# satshakit.net
KiCad netlist of a schematic drawn in EAGLE
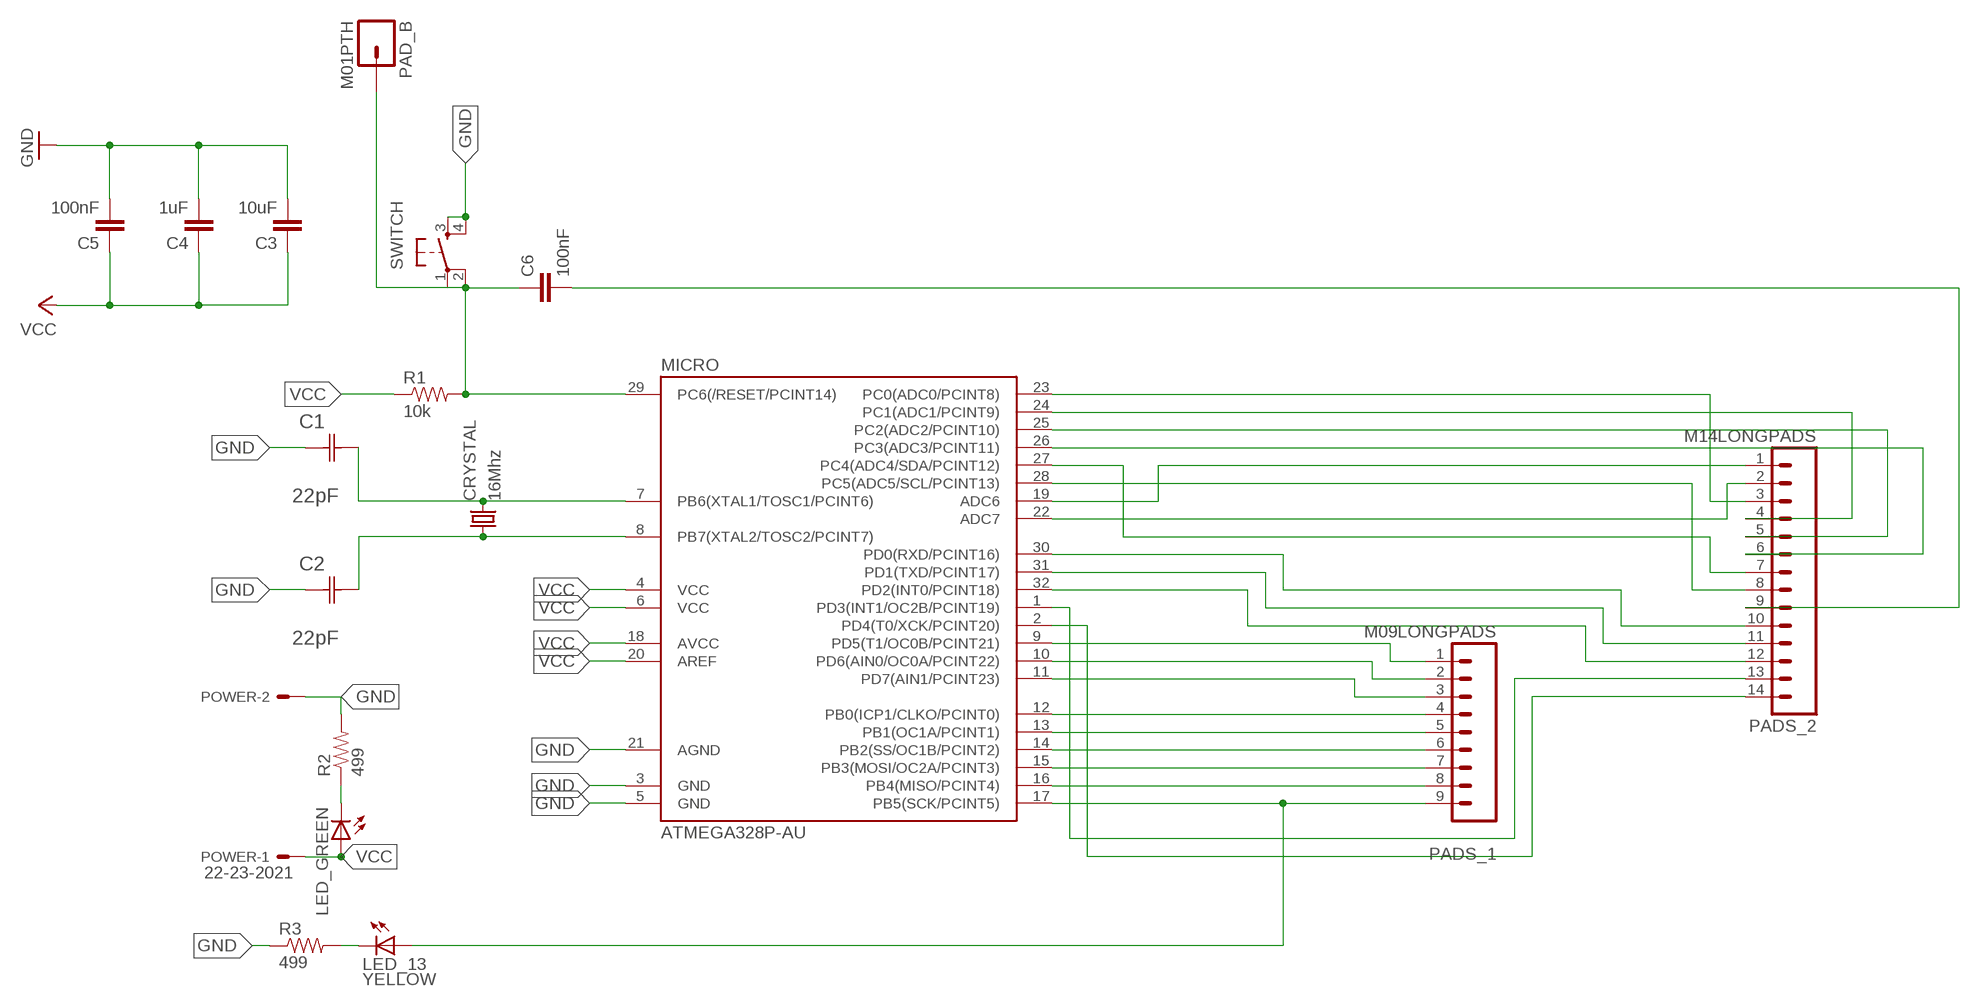
[diagram p0: schematic, sheet 1]

(export (version "E")
  (design (tool "Eeschema 10.0.6"))
  (components
    (comp (ref "C1")
      (value "22pF")
      (footprint "eagle-import:CAPC3216X178N")
      (fields (field (name "MPN") "0612ZC225MAT2A") (field (name "TOLERANCE") "±20%"))
      (libsource (lib "eagle-import") (part "0612ZC225MAT2A"))
    )
    (comp (ref "C2")
      (value "22pF")
      (footprint "eagle-import:CAPC3216X178N")
      (fields (field (name "MPN") "0612ZC225MAT2A") (field (name "TOLERANCE") "±20%"))
      (libsource (lib "eagle-import") (part "0612ZC225MAT2A"))
    )
    (comp (ref "C3")
      (value "10uF")
      (footprint "eagle-import:1206")
      (libsource (lib "eagle-import") (part "CAP1206"))
    )
    (comp (ref "C4")
      (value "1uF")
      (footprint "eagle-import:1206")
      (libsource (lib "eagle-import") (part "CAP1206"))
    )
    (comp (ref "C5")
      (value "100nF")
      (footprint "eagle-import:1206")
      (libsource (lib "eagle-import") (part "CAP1206"))
    )
    (comp (ref "C6")
      (value "100nF")
      (footprint "eagle-import:1206")
      (libsource (lib "eagle-import") (part "CAP1206"))
    )
    (comp (ref "CRYSTAL")
      (value "16Mhz")
      (footprint "eagle-import:CSM-7X-DU")
      (libsource (lib "eagle-import") (part "CSM-7X-DU"))
    )
    (comp (ref "LED_13")
      (value "YELLOW")
      (footprint "eagle-import:1206")
      (libsource (lib "eagle-import") (part "LED1206"))
    )
    (comp (ref "LED_GREEN")
      (value "LED1206")
      (footprint "eagle-import:1206")
      (libsource (lib "eagle-import") (part "LED1206"))
    )
    (comp (ref "MICRO")
      (value "ATMEGA328P-AU")
      (footprint "eagle-import:TQFP32-08")
      (libsource (lib "eagle-import") (part "ATMEGA48/88/168-AU"))
    )
    (comp (ref "PADS_1")
      (value "M09LONGPADS")
      (footprint "eagle-import:1X09_LONGPADS")
      (libsource (lib "eagle-import") (part "M09LONGPADS"))
    )
    (comp (ref "PADS_2")
      (value "M14LONGPADS")
      (footprint "eagle-import:1X14-LONGPADS")
      (libsource (lib "eagle-import") (part "M14LONGPADS"))
    )
    (comp (ref "PAD_B")
      (value "M01PTH")
      (footprint "eagle-import:1X01")
      (libsource (lib "eagle-import") (part "M01PTH"))
    )
    (comp (ref "POWER")
      (value "22-23-2021")
      (footprint "eagle-import:22-23-2021")
      (fields (field (name "MF") "MOLEX"))
      (libsource (lib "eagle-import") (part "22-23-2021"))
    )
    (comp (ref "R1")
      (value "10k")
      (footprint "eagle-import:1206")
      (libsource (lib "eagle-import") (part "RESISTOR1206"))
    )
    (comp (ref "R2")
      (value "499")
      (footprint "eagle-import:1206")
      (libsource (lib "eagle-import") (part "RESISTOR1206"))
    )
    (comp (ref "R3")
      (value "499")
      (footprint "eagle-import:1206")
      (libsource (lib "eagle-import") (part "RESISTOR1206"))
    )
    (comp (ref "SWITCH")
      (value "6MM_SWITCH6MM_SWITCH")
      (footprint "eagle-import:6MM_SWITCH")
      (libsource (lib "eagle-import") (part "6MM_SWITCH6MM_SWITCH"))
    )
  )
  (nets
    (net (code "1") (name "GND") (class "Default")
      (node (ref "C1") (pin "1") (pinfunction "C1_1") (pintype "passive"))
      (node (ref "C2") (pin "1") (pinfunction "C1_1") (pintype "passive"))
      (node (ref "C3") (pin "2") (pinfunction "2_2") (pintype "passive"))
      (node (ref "C4") (pin "2") (pinfunction "2_2") (pintype "passive"))
      (node (ref "C5") (pin "2") (pinfunction "2_2") (pintype "passive"))
      (node (ref "MICRO") (pin "21") (pinfunction "AGND_21") (pintype "power_in"))
      (node (ref "MICRO") (pin "3") (pinfunction "GND_3") (pintype "power_in"))
      (node (ref "MICRO") (pin "5") (pinfunction "GND_5") (pintype "power_in"))
      (node (ref "POWER") (pin "2") (pinfunction "S_2") (pintype "passive"))
      (node (ref "R2") (pin "2") (pinfunction "2_2") (pintype "passive"))
      (node (ref "R3") (pin "1") (pinfunction "1_1") (pintype "passive"))
      (node (ref "SWITCH") (pin "3") (pinfunction "S_3") (pintype "passive"))
      (node (ref "SWITCH") (pin "4") (pinfunction "S1_4") (pintype "passive"))
    )
    (net (code "2") (name "Net-(C1-C2)") (class "Default")
      (node (ref "C1") (pin "2") (pinfunction "C2_2") (pintype "passive"))
      (node (ref "CRYSTAL") (pin "2") (pinfunction "2_2") (pintype "passive"))
      (node (ref "MICRO") (pin "7") (pinfunction "PB6(XTAL1/TOSC1/PCINT6)_7") (pintype "bidirectional"))
    )
    (net (code "3") (name "Net-(C2-C2)") (class "Default")
      (node (ref "C2") (pin "2") (pinfunction "C2_2") (pintype "passive"))
      (node (ref "CRYSTAL") (pin "1") (pinfunction "1_1") (pintype "passive"))
      (node (ref "MICRO") (pin "8") (pinfunction "PB7(XTAL2/TOSC2/PCINT7)_8") (pintype "bidirectional"))
    )
    (net (code "4") (name "Net-(C6-Pad2)") (class "Default")
      (node (ref "C6") (pin "2") (pinfunction "2_2") (pintype "passive"))
      (node (ref "PADS_2") (pin "9") (pinfunction "9_9") (pintype "passive"))
    )
    (net (code "5") (name "Net-(LED_13-A)") (class "Default")
      (node (ref "LED_13") (pin "1") (pinfunction "A_1") (pintype "passive"))
      (node (ref "MICRO") (pin "17") (pinfunction "PB5(SCK/PCINT5)_17") (pintype "bidirectional"))
      (node (ref "PADS_1") (pin "9") (pinfunction "9_9") (pintype "passive"))
    )
    (net (code "6") (name "Net-(LED_13-C)") (class "Default")
      (node (ref "LED_13") (pin "2") (pinfunction "C_2") (pintype "passive"))
      (node (ref "R3") (pin "2") (pinfunction "2_2") (pintype "passive"))
    )
    (net (code "7") (name "Net-(LED_GREEN-C)") (class "Default")
      (node (ref "LED_GREEN") (pin "2") (pinfunction "C_2") (pintype "passive"))
      (node (ref "R2") (pin "1") (pinfunction "1_1") (pintype "passive"))
    )
    (net (code "8") (name "Net-(MICRO-ADC6)") (class "Default")
      (node (ref "MICRO") (pin "19") (pinfunction "ADC6_19") (pintype "passive"))
      (node (ref "PADS_2") (pin "1") (pinfunction "1_1") (pintype "passive"))
    )
    (net (code "9") (name "Net-(MICRO-ADC7)") (class "Default")
      (node (ref "MICRO") (pin "22") (pinfunction "ADC7_22") (pintype "passive"))
      (node (ref "PADS_2") (pin "2") (pinfunction "2_2") (pintype "passive"))
    )
    (net (code "10") (name "Net-(MICRO-PB0(ICP1{slash}CLKO{slash}PCINT0))") (class "Default")
      (node (ref "MICRO") (pin "12") (pinfunction "PB0(ICP1/CLKO/PCINT0)_12") (pintype "bidirectional"))
      (node (ref "PADS_1") (pin "4") (pinfunction "4_4") (pintype "passive"))
    )
    (net (code "11") (name "Net-(MICRO-PB1(OC1A{slash}PCINT1))") (class "Default")
      (node (ref "MICRO") (pin "13") (pinfunction "PB1(OC1A/PCINT1)_13") (pintype "bidirectional"))
      (node (ref "PADS_1") (pin "5") (pinfunction "5_5") (pintype "passive"))
    )
    (net (code "12") (name "Net-(MICRO-PB2(SS{slash}OC1B{slash}PCINT2))") (class "Default")
      (node (ref "MICRO") (pin "14") (pinfunction "PB2(SS/OC1B/PCINT2)_14") (pintype "bidirectional"))
      (node (ref "PADS_1") (pin "6") (pinfunction "6_6") (pintype "passive"))
    )
    (net (code "13") (name "Net-(MICRO-PB3(MOSI{slash}OC2A{slash}PCINT3))") (class "Default")
      (node (ref "MICRO") (pin "15") (pinfunction "PB3(MOSI/OC2A/PCINT3)_15") (pintype "bidirectional"))
      (node (ref "PADS_1") (pin "7") (pinfunction "7_7") (pintype "passive"))
    )
    (net (code "14") (name "Net-(MICRO-PB4(MISO{slash}PCINT4))") (class "Default")
      (node (ref "MICRO") (pin "16") (pinfunction "PB4(MISO/PCINT4)_16") (pintype "bidirectional"))
      (node (ref "PADS_1") (pin "8") (pinfunction "8_8") (pintype "passive"))
    )
    (net (code "15") (name "Net-(MICRO-PC0(ADC0{slash}PCINT8))") (class "Default")
      (node (ref "MICRO") (pin "23") (pinfunction "PC0(ADC0/PCINT8)_23") (pintype "bidirectional"))
      (node (ref "PADS_2") (pin "3") (pinfunction "3_3") (pintype "passive"))
    )
    (net (code "16") (name "Net-(MICRO-PC1(ADC1{slash}PCINT9))") (class "Default")
      (node (ref "MICRO") (pin "24") (pinfunction "PC1(ADC1/PCINT9)_24") (pintype "bidirectional"))
      (node (ref "PADS_2") (pin "4") (pinfunction "4_4") (pintype "passive"))
    )
    (net (code "17") (name "Net-(MICRO-PC2(ADC2{slash}PCINT10))") (class "Default")
      (node (ref "MICRO") (pin "25") (pinfunction "PC2(ADC2/PCINT10)_25") (pintype "bidirectional"))
      (node (ref "PADS_2") (pin "5") (pinfunction "5_5") (pintype "passive"))
    )
    (net (code "18") (name "Net-(MICRO-PC3(ADC3{slash}PCINT11))") (class "Default")
      (node (ref "MICRO") (pin "26") (pinfunction "PC3(ADC3/PCINT11)_26") (pintype "bidirectional"))
      (node (ref "PADS_2") (pin "6") (pinfunction "6_6") (pintype "passive"))
    )
    (net (code "19") (name "Net-(MICRO-PC4(ADC4{slash}SDA{slash}PCINT12))") (class "Default")
      (node (ref "MICRO") (pin "27") (pinfunction "PC4(ADC4/SDA/PCINT12)_27") (pintype "bidirectional"))
      (node (ref "PADS_2") (pin "7") (pinfunction "7_7") (pintype "passive"))
    )
    (net (code "20") (name "Net-(MICRO-PC5(ADC5{slash}SCL{slash}PCINT13))") (class "Default")
      (node (ref "MICRO") (pin "28") (pinfunction "PC5(ADC5/SCL/PCINT13)_28") (pintype "bidirectional"))
      (node (ref "PADS_2") (pin "8") (pinfunction "8_8") (pintype "passive"))
    )
    (net (code "21") (name "Net-(MICRO-PC6({slash}RESET{slash}PCINT14))") (class "Default")
      (node (ref "C6") (pin "1") (pinfunction "1_1") (pintype "passive"))
      (node (ref "MICRO") (pin "29") (pinfunction "PC6(/RESET/PCINT14)_29") (pintype "bidirectional"))
      (node (ref "PAD_B") (pin "1") (pinfunction "1_1") (pintype "passive"))
      (node (ref "R1") (pin "2") (pinfunction "2_2") (pintype "passive"))
      (node (ref "SWITCH") (pin "1") (pinfunction "P_1") (pintype "passive"))
      (node (ref "SWITCH") (pin "2") (pinfunction "P1_2") (pintype "passive"))
    )
    (net (code "22") (name "Net-(MICRO-PD0(RXD{slash}PCINT16))") (class "Default")
      (node (ref "MICRO") (pin "30") (pinfunction "PD0(RXD/PCINT16)_30") (pintype "bidirectional"))
      (node (ref "PADS_2") (pin "10") (pinfunction "10_10") (pintype "passive"))
    )
    (net (code "23") (name "Net-(MICRO-PD1(TXD{slash}PCINT17))") (class "Default")
      (node (ref "MICRO") (pin "31") (pinfunction "PD1(TXD/PCINT17)_31") (pintype "bidirectional"))
      (node (ref "PADS_2") (pin "11") (pinfunction "11_11") (pintype "passive"))
    )
    (net (code "24") (name "Net-(MICRO-PD2(INT0{slash}PCINT18))") (class "Default")
      (node (ref "MICRO") (pin "32") (pinfunction "PD2(INT0/PCINT18)_32") (pintype "bidirectional"))
      (node (ref "PADS_2") (pin "12") (pinfunction "12_12") (pintype "passive"))
    )
    (net (code "25") (name "Net-(MICRO-PD3(INT1{slash}OC2B{slash}PCINT19))") (class "Default")
      (node (ref "MICRO") (pin "1") (pinfunction "PD3(INT1/OC2B/PCINT19)_1") (pintype "bidirectional"))
      (node (ref "PADS_2") (pin "13") (pinfunction "13_13") (pintype "passive"))
    )
    (net (code "26") (name "Net-(MICRO-PD4(T0{slash}XCK{slash}PCINT20))") (class "Default")
      (node (ref "MICRO") (pin "2") (pinfunction "PD4(T0/XCK/PCINT20)_2") (pintype "bidirectional"))
      (node (ref "PADS_2") (pin "14") (pinfunction "14_14") (pintype "passive"))
    )
    (net (code "27") (name "Net-(MICRO-PD5(T1{slash}OC0B{slash}PCINT21))") (class "Default")
      (node (ref "MICRO") (pin "9") (pinfunction "PD5(T1/OC0B/PCINT21)_9") (pintype "bidirectional"))
      (node (ref "PADS_1") (pin "1") (pinfunction "1_1") (pintype "passive"))
    )
    (net (code "28") (name "Net-(MICRO-PD6(AIN0{slash}OC0A{slash}PCINT22))") (class "Default")
      (node (ref "MICRO") (pin "10") (pinfunction "PD6(AIN0/OC0A/PCINT22)_10") (pintype "bidirectional"))
      (node (ref "PADS_1") (pin "2") (pinfunction "2_2") (pintype "passive"))
    )
    (net (code "29") (name "Net-(MICRO-PD7(AIN1{slash}PCINT23))") (class "Default")
      (node (ref "MICRO") (pin "11") (pinfunction "PD7(AIN1/PCINT23)_11") (pintype "bidirectional"))
      (node (ref "PADS_1") (pin "3") (pinfunction "3_3") (pintype "passive"))
    )
    (net (code "30") (name "VCC") (class "Default")
      (node (ref "C3") (pin "1") (pinfunction "1_1") (pintype "passive"))
      (node (ref "C4") (pin "1") (pinfunction "1_1") (pintype "passive"))
      (node (ref "C5") (pin "1") (pinfunction "1_1") (pintype "passive"))
      (node (ref "LED_GREEN") (pin "1") (pinfunction "A_1") (pintype "passive"))
      (node (ref "MICRO") (pin "18") (pinfunction "AVCC_18") (pintype "passive"))
      (node (ref "MICRO") (pin "20") (pinfunction "AREF_20") (pintype "passive"))
      (node (ref "MICRO") (pin "4") (pinfunction "VCC_4") (pintype "power_in"))
      (node (ref "MICRO") (pin "6") (pinfunction "VCC_6") (pintype "power_in"))
      (node (ref "POWER") (pin "1") (pinfunction "S_1") (pintype "passive"))
      (node (ref "R1") (pin "1") (pinfunction "1_1") (pintype "passive"))
    )
  )
)
